# IMUCubePIN_Sch.net
KiCad netlist of a schematic drawn in Altium Designer
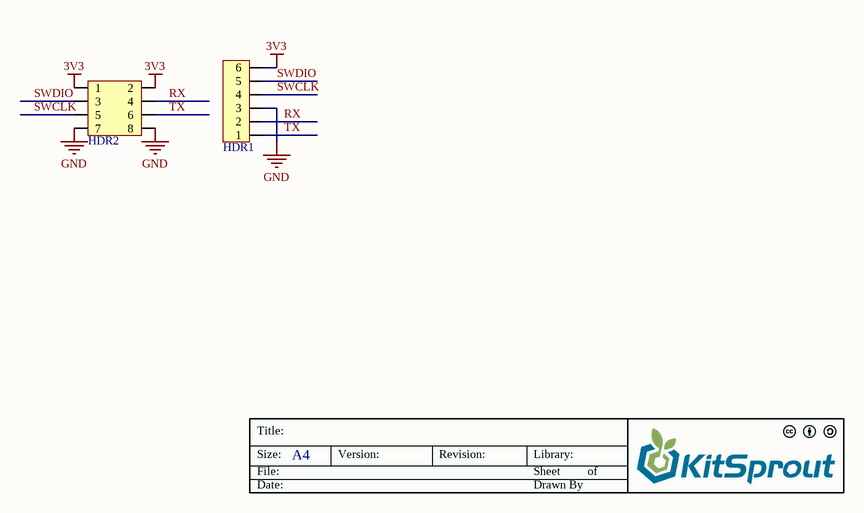
[diagram p0: IMUCubePIN_Sch.SchDoc]

(export (version "E")
  (design (tool "Eeschema 10.0.6"))
  (components
    (comp (ref "HDR1")
      (value "HDR1x6_1.27")
      (footprint "PCB_ConnectorHDR:HDR1X6_1.27_180H")
      (description "Header")
      (libsource (lib "SCH_ConnectorHDR") (part "HDR1x6_1.27"))
    )
    (comp (ref "HDR2")
      (value "HDR2x4_2.54")
      (footprint "PCB_ConnectorHDR:HDR2X4_2.54_180H")
      (description "Header")
      (libsource (lib "SCH_ConnectorHDR") (part "HDR2x4_2.54"))
    )
  )
  (nets
    (net (code "1") (name "/RX") (class "Default")
      (node (ref "HDR1") (pin "2") (pinfunction "2_2") (pintype "passive"))
      (node (ref "HDR2") (pin "4") (pinfunction "4_4") (pintype "passive"))
    )
    (net (code "2") (name "/SWCLK") (class "Default")
      (node (ref "HDR1") (pin "4") (pinfunction "4_4") (pintype "passive"))
      (node (ref "HDR2") (pin "5") (pinfunction "5_5") (pintype "passive"))
    )
    (net (code "3") (name "/SWDIO") (class "Default")
      (node (ref "HDR1") (pin "5") (pinfunction "5_5") (pintype "passive"))
      (node (ref "HDR2") (pin "3") (pinfunction "3_3") (pintype "passive"))
    )
    (net (code "4") (name "/TX") (class "Default")
      (node (ref "HDR1") (pin "1") (pinfunction "1_1") (pintype "passive"))
      (node (ref "HDR2") (pin "6") (pinfunction "6_6") (pintype "passive"))
    )
    (net (code "5") (name "3V3") (class "Default")
      (node (ref "HDR1") (pin "6") (pinfunction "6_6") (pintype "passive"))
      (node (ref "HDR2") (pin "1") (pinfunction "1_1") (pintype "passive"))
      (node (ref "HDR2") (pin "2") (pinfunction "2_2") (pintype "passive"))
    )
    (net (code "6") (name "GND") (class "Default")
      (node (ref "HDR1") (pin "3") (pinfunction "3_3") (pintype "passive"))
      (node (ref "HDR2") (pin "7") (pinfunction "7_7") (pintype "passive"))
      (node (ref "HDR2") (pin "8") (pinfunction "8_8") (pintype "passive"))
    )
  )
)
